# TH8_USB.net
KiCad netlist of a schematic drawn in Altium Designer
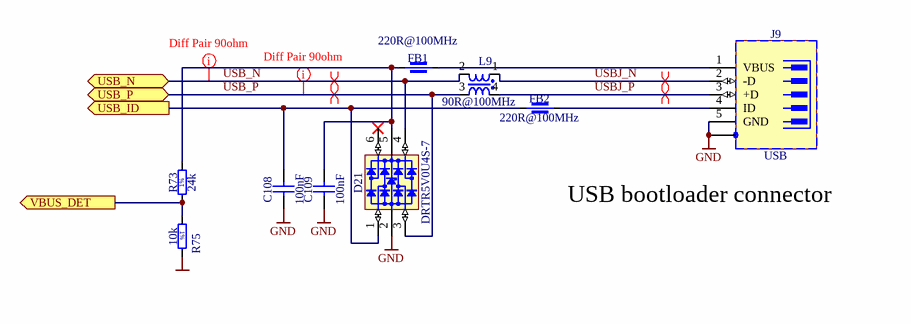
[diagram p0: TH8_USB.SchDoc]

(export (version "E")
  (design (tool "Eeschema 10.0.6"))
  (components
    (comp (ref "C108")
      (value "100nF")
      (footprint "CAPC1005X55N")
      (description "Non-polarised capacitor")
      (fields
        (field (name "PART NUMBER") "CC0402_100NF_16V_10%_X7R")
        (field (name "VOLTAGE") "16V")
        (field (name "AUTHOR") "CERN DEM JLC")
      )
      (libsource (lib "Capacitors") (part "Capacitor - non polarized"))
    )
    (comp (ref "C109")
      (value "100nF")
      (footprint "CAPC1005X55N")
      (description "Non-polarised capacitor")
      (fields
        (field (name "PART NUMBER") "CC0402_100NF_16V_10%_X7R")
        (field (name "VOLTAGE") "16V")
        (field (name "AUTHOR") "CERN DEM JLC")
      )
      (libsource (lib "Capacitors") (part "Capacitor - non polarized"))
    )
    (comp (ref "D21")
      (value "DRTR5V0U4S-7")
      (footprint "SOT65P210X110-6N")
      (description "Integrated Quad Ultra-Low Capacitance ESD Protection")
      (fields (field (name "MANUFACTURER") "DIODES") (field (name "AUTHOR") "GK"))
      (libsource (lib "Diodes") (part "D_TVS_DRTR5V0U4S-7"))
    )
    (comp (ref "FB1")
      (value "220R@100MHz")
      (footprint "INDC1005X55N")
      (fields
        (field (name "PART NUMBER") "IND0402_MURATA_BLM15HB221SN1")
        (field (name "POWER") "250mA")
        (field (name "TOLERANCE") "±25%")
        (field (name "AUTHOR") "CERN DEM JLC")
      )
      (libsource (lib "Inductors & Transformers") (part "Ferrite Bead"))
    )
    (comp (ref "FB2")
      (value "220R@100MHz")
      (footprint "INDC1005X55N")
      (fields
        (field (name "PART NUMBER") "IND0402_MURATA_BLM15HB221SN1")
        (field (name "POWER") "250mA")
        (field (name "TOLERANCE") "±25%")
        (field (name "AUTHOR") "CERN DEM JLC")
      )
      (libsource (lib "Inductors & Transformers") (part "Ferrite Bead"))
    )
    (comp (ref "J9")
      (value "USB")
      (footprint "UJ2-MIBH-4-MSMT")
      (description "5 Pin + 1 Shield  in-line USB Receptacle")
      (fields
        (field (name "PART NUMBER") "CUI_UJ2-MIBH-4-MSMT")
        (field (name "MANUFACTURER") "CUI")
        (field (name "AUTHOR") "GK")
      )
      (libsource (lib "LIBRARY_SCH") (part "CON_USB_UJ2-MIBH-4-MSMT"))
    )
    (comp (ref "L9")
      (value "90R@100MHz")
      (footprint "IND_MURATA_DLW21S")
      (description "Inductor Common Mode")
      (fields
        (field (name "PART NUMBER") "IND_MURATA_DLW21SN900SQ2L")
        (field (name "POWER") "330mA")
        (field (name "AUTHOR") "CERN DEM JLC")
      )
      (libsource (lib "Inductors & Transformers") (part "Inductor Common Mode 1Dot-2 4Dot-3"))
    )
    (comp (ref "R73")
      (value "24k")
      (footprint "RESC1608X55N")
      (description "Resistor - 1%")
      (fields
        (field (name "PART NUMBER") "R0603_24K_1%_0.1W_100PPM")
        (field (name "POWER") "0.1W")
        (field (name "AUTHOR") "CERN DEM JLC")
      )
      (libsource (lib "Resistors") (part "Resistor - 1%"))
    )
    (comp (ref "R75")
      (value "10k")
      (footprint "RESC1005X40N")
      (description "Resistor - 1%")
      (fields
        (field (name "PART NUMBER") "R0402_10K_1%_0.0625W_100PPM")
        (field (name "POWER") "0.0625W")
        (field (name "AUTHOR") "CERN DEM JLC")
      )
      (libsource (lib "Resistors") (part "Resistor - 1%"))
    )
  )
  (nets
    (net (code "1") (name "/USBJ_N") (class "Default")
      (node (ref "J9") (pin "2") (pinfunction "-D_2") (pintype "bidirectional"))
      (node (ref "L9") (pin "1") (pinfunction "1_1") (pintype "passive"))
    )
    (net (code "2") (name "/USBJ_P") (class "Default")
      (node (ref "J9") (pin "3") (pinfunction "+D_3") (pintype "bidirectional"))
      (node (ref "L9") (pin "4") (pinfunction "4_4") (pintype "passive"))
    )
    (net (code "3") (name "/USB_ID") (class "Default")
      (node (ref "C108") (pin "2") (pinfunction "2_2") (pintype "passive"))
      (node (ref "D21") (pin "1") (pinfunction "I/O1_1") (pintype "bidirectional"))
      (node (ref "FB2") (pin "1") (pinfunction "1_1") (pintype "passive"))
    )
    (net (code "4") (name "/USB_N") (class "Default")
      (node (ref "D21") (pin "4") (pinfunction "I/O3_4") (pintype "bidirectional"))
      (node (ref "L9") (pin "2") (pinfunction "2_2") (pintype "passive"))
    )
    (net (code "5") (name "/USB_P") (class "Default")
      (node (ref "D21") (pin "3") (pinfunction "I/O2_3") (pintype "bidirectional"))
      (node (ref "L9") (pin "3") (pinfunction "3_3") (pintype "passive"))
    )
    (net (code "6") (name "/VBUS_DET") (class "Default")
      (node (ref "R73") (pin "1") (pinfunction "1_1") (pintype "passive"))
      (node (ref "R75") (pin "1") (pinfunction "1_1") (pintype "passive"))
    )
    (net (code "7") (name "GND") (class "Default")
      (node (ref "C108") (pin "1") (pinfunction "1_1") (pintype "passive"))
      (node (ref "C109") (pin "1") (pinfunction "1_1") (pintype "passive"))
      (node (ref "D21") (pin "2") (pinfunction "GND_2") (pintype "power_in"))
      (node (ref "J9") (pin "10") (pinfunction "SH_10") (pintype "power_in"))
      (node (ref "J9") (pin "11") (pinfunction "SH_11") (pintype "power_in"))
      (node (ref "J9") (pin "5") (pinfunction "GND_5") (pintype "power_in"))
      (node (ref "J9") (pin "6") (pinfunction "SH_6") (pintype "power_in"))
      (node (ref "J9") (pin "7") (pinfunction "SH_7") (pintype "power_in"))
      (node (ref "J9") (pin "8") (pinfunction "SH_8") (pintype "power_in"))
      (node (ref "J9") (pin "9") (pinfunction "SH_9") (pintype "power_in"))
      (node (ref "R75") (pin "2") (pinfunction "2_2") (pintype "passive"))
    )
    (net (code "8") (name "Net-(D21-VBUS)") (class "Default")
      (node (ref "C109") (pin "2") (pinfunction "2_2") (pintype "passive"))
      (node (ref "D21") (pin "5") (pinfunction "VBUS_5") (pintype "power_in"))
      (node (ref "FB1") (pin "1") (pinfunction "1_1") (pintype "passive"))
      (node (ref "R73") (pin "2") (pinfunction "2_2") (pintype "passive"))
    )
    (net (code "9") (name "Net-(J9-ID)") (class "Default")
      (node (ref "FB2") (pin "2") (pinfunction "2_2") (pintype "passive"))
      (node (ref "J9") (pin "4") (pinfunction "ID_4") (pintype "passive"))
    )
    (net (code "10") (name "Net-(J9-VBUS)") (class "Default")
      (node (ref "FB1") (pin "2") (pinfunction "2_2") (pintype "passive"))
      (node (ref "J9") (pin "1") (pinfunction "VBUS_1") (pintype "power_in"))
    )
    (net (code "11") (name "unconnected-(D21-I{slash}O4-Pad6)") (class "Default")
      (node (ref "D21") (pin "6") (pinfunction "I/O4_6") (pintype "bidirectional+no_connect"))
    )
  )
)
